# Keg_Cop_-_Eight_Straight.net
KiCad netlist of a schematic drawn in EAGLE
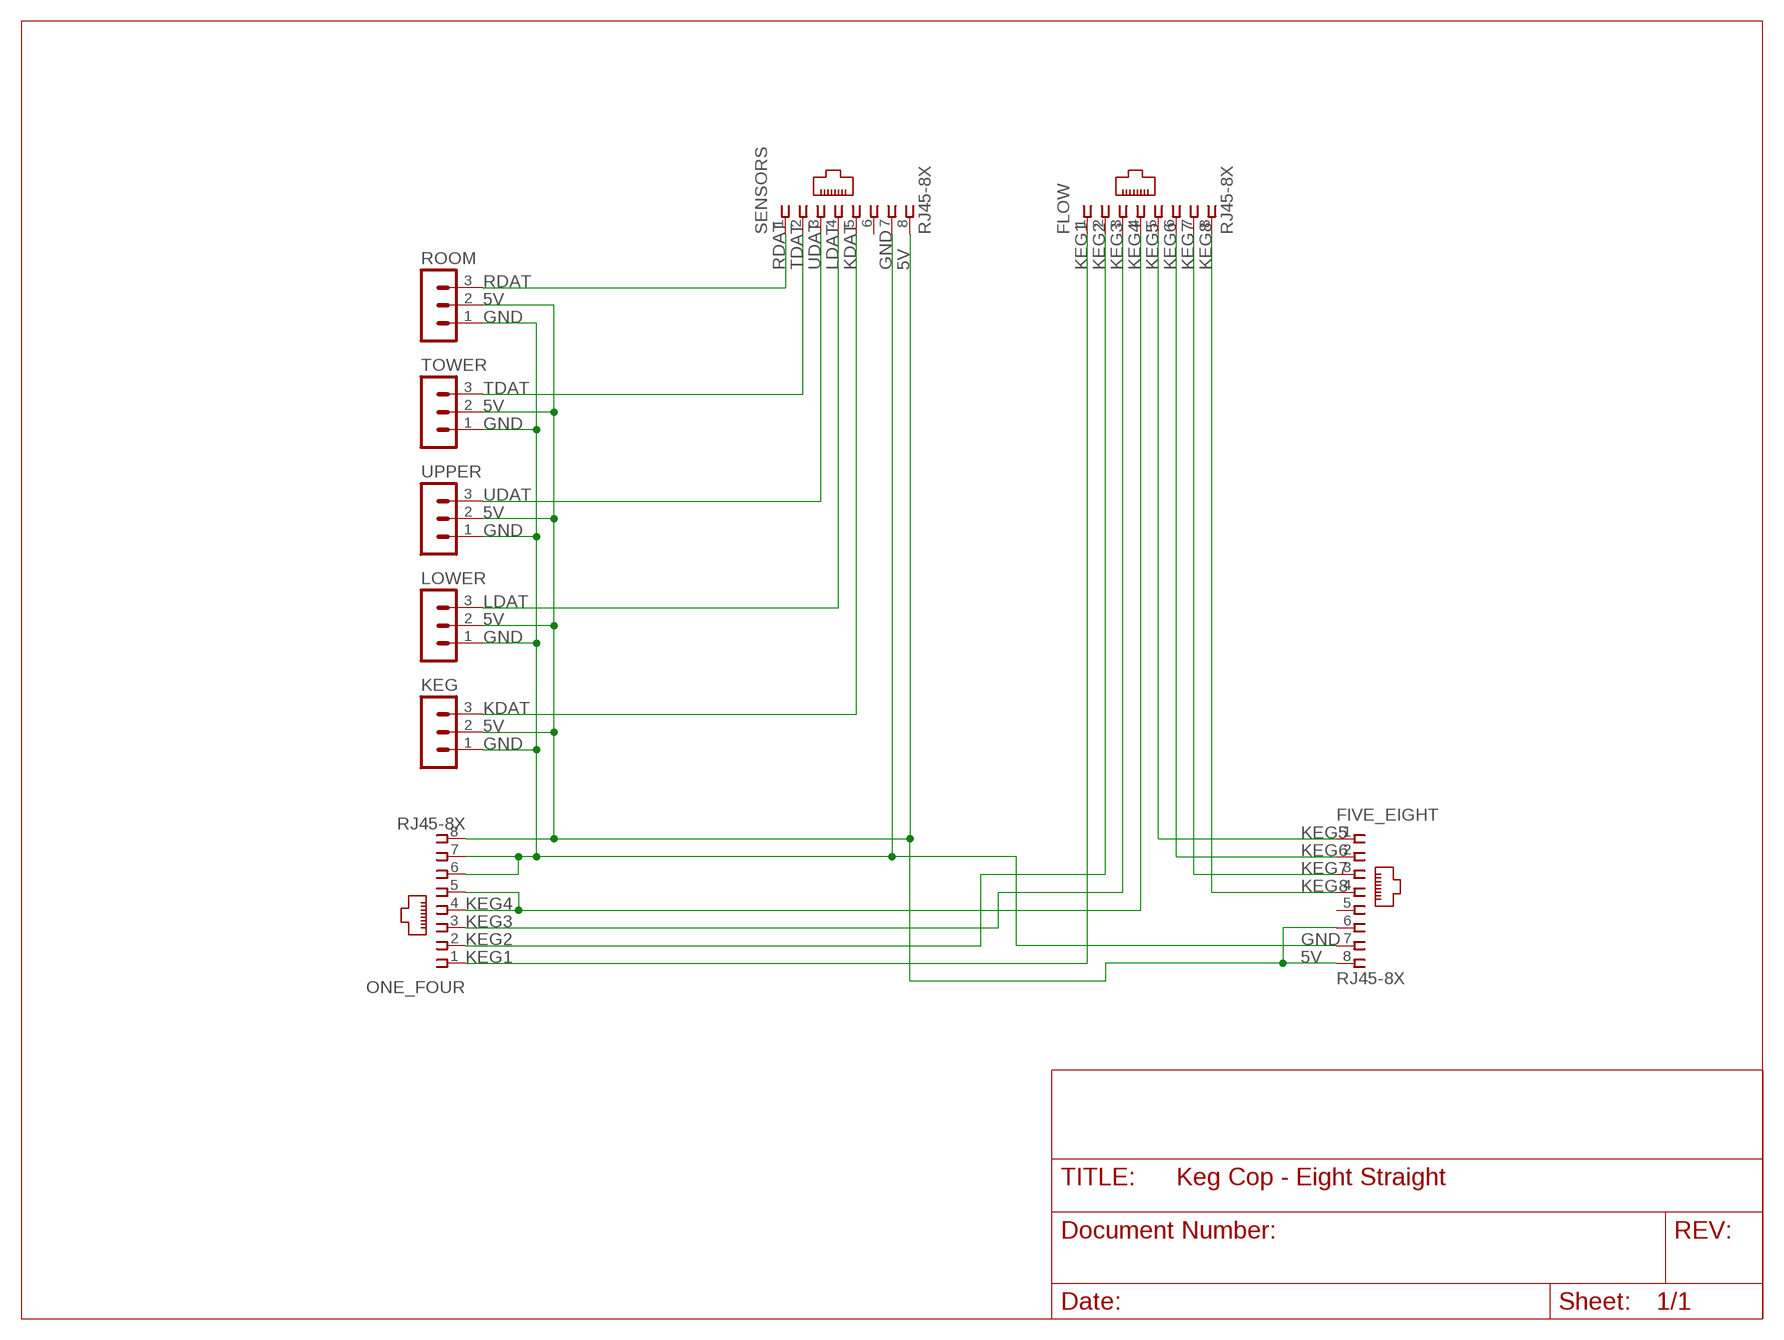
[diagram p0: schematic, sheet 1]

(export (version "E")
  (design (tool "Eeschema 10.0.6"))
  (components
    (comp (ref "FIVE_EIGHT")
      (value "RJ45-8X")
      (footprint "eagle-import:RJ45-NO-SHIELD")
      (libsource (lib "eagle-import") (part "RJ45-8X"))
    )
    (comp (ref "FLOW")
      (value "RJ45-8X")
      (footprint "eagle-import:RJ45-NO-SHIELD")
      (libsource (lib "eagle-import") (part "RJ45-8X"))
    )
    (comp (ref "KEG")
      (value "HDR-3")
      (footprint "eagle-import:HDR-3_VERT")
      (libsource (lib "eagle-import") (part "HDR-3"))
    )
    (comp (ref "LOWER")
      (value "HDR-3")
      (footprint "eagle-import:HDR-3_VERT")
      (libsource (lib "eagle-import") (part "HDR-3"))
    )
    (comp (ref "ONE_FOUR")
      (value "RJ45-8X")
      (footprint "eagle-import:RJ45-NO-SHIELD")
      (libsource (lib "eagle-import") (part "RJ45-8X"))
    )
    (comp (ref "ROOM")
      (value "HDR-3")
      (footprint "eagle-import:HDR-3_VERT")
      (libsource (lib "eagle-import") (part "HDR-3"))
    )
    (comp (ref "SENSORS")
      (value "RJ45-8X")
      (footprint "eagle-import:RJ45-NO-SHIELD")
      (libsource (lib "eagle-import") (part "RJ45-8X"))
    )
    (comp (ref "TOWER")
      (value "HDR-3")
      (footprint "eagle-import:HDR-3_VERT")
      (libsource (lib "eagle-import") (part "HDR-3"))
    )
    (comp (ref "UPPER")
      (value "HDR-3")
      (footprint "eagle-import:HDR-3_VERT")
      (libsource (lib "eagle-import") (part "HDR-3"))
    )
  )
  (nets
    (net (code "1") (name "/5V") (class "Default")
      (node (ref "FIVE_EIGHT") (pin "6") (pinfunction "6_6") (pintype "passive"))
      (node (ref "FIVE_EIGHT") (pin "8") (pinfunction "8_8") (pintype "passive"))
      (node (ref "KEG") (pin "2") (pinfunction "2_2") (pintype "passive"))
      (node (ref "LOWER") (pin "2") (pinfunction "2_2") (pintype "passive"))
      (node (ref "ONE_FOUR") (pin "8") (pinfunction "8_8") (pintype "passive"))
      (node (ref "ROOM") (pin "2") (pinfunction "2_2") (pintype "passive"))
      (node (ref "SENSORS") (pin "8") (pinfunction "8_8") (pintype "passive"))
      (node (ref "TOWER") (pin "2") (pinfunction "2_2") (pintype "passive"))
      (node (ref "UPPER") (pin "2") (pinfunction "2_2") (pintype "passive"))
    )
    (net (code "2") (name "/GND") (class "Default")
      (node (ref "FIVE_EIGHT") (pin "7") (pinfunction "7_7") (pintype "passive"))
      (node (ref "KEG") (pin "1") (pinfunction "1_1") (pintype "passive"))
      (node (ref "LOWER") (pin "1") (pinfunction "1_1") (pintype "passive"))
      (node (ref "ONE_FOUR") (pin "6") (pinfunction "6_6") (pintype "passive"))
      (node (ref "ONE_FOUR") (pin "7") (pinfunction "7_7") (pintype "passive"))
      (node (ref "ROOM") (pin "1") (pinfunction "1_1") (pintype "passive"))
      (node (ref "SENSORS") (pin "7") (pinfunction "7_7") (pintype "passive"))
      (node (ref "TOWER") (pin "1") (pinfunction "1_1") (pintype "passive"))
      (node (ref "UPPER") (pin "1") (pinfunction "1_1") (pintype "passive"))
    )
    (net (code "3") (name "/KDAT") (class "Default")
      (node (ref "KEG") (pin "3") (pinfunction "3_3") (pintype "passive"))
      (node (ref "SENSORS") (pin "5") (pinfunction "5_5") (pintype "passive"))
    )
    (net (code "4") (name "/KEG1") (class "Default")
      (node (ref "FLOW") (pin "1") (pinfunction "1_1") (pintype "passive"))
      (node (ref "ONE_FOUR") (pin "1") (pinfunction "1_1") (pintype "passive"))
    )
    (net (code "5") (name "/KEG2") (class "Default")
      (node (ref "FLOW") (pin "2") (pinfunction "2_2") (pintype "passive"))
      (node (ref "ONE_FOUR") (pin "2") (pinfunction "2_2") (pintype "passive"))
    )
    (net (code "6") (name "/KEG3") (class "Default")
      (node (ref "FLOW") (pin "3") (pinfunction "3_3") (pintype "passive"))
      (node (ref "ONE_FOUR") (pin "3") (pinfunction "3_3") (pintype "passive"))
    )
    (net (code "7") (name "/KEG4") (class "Default")
      (node (ref "FLOW") (pin "4") (pinfunction "4_4") (pintype "passive"))
      (node (ref "ONE_FOUR") (pin "4") (pinfunction "4_4") (pintype "passive"))
      (node (ref "ONE_FOUR") (pin "5") (pinfunction "5_5") (pintype "passive"))
    )
    (net (code "8") (name "/KEG5") (class "Default")
      (node (ref "FIVE_EIGHT") (pin "1") (pinfunction "1_1") (pintype "passive"))
      (node (ref "FLOW") (pin "5") (pinfunction "5_5") (pintype "passive"))
    )
    (net (code "9") (name "/KEG6") (class "Default")
      (node (ref "FIVE_EIGHT") (pin "2") (pinfunction "2_2") (pintype "passive"))
      (node (ref "FLOW") (pin "6") (pinfunction "6_6") (pintype "passive"))
    )
    (net (code "10") (name "/KEG7") (class "Default")
      (node (ref "FIVE_EIGHT") (pin "3") (pinfunction "3_3") (pintype "passive"))
      (node (ref "FLOW") (pin "7") (pinfunction "7_7") (pintype "passive"))
    )
    (net (code "11") (name "/KEG8") (class "Default")
      (node (ref "FIVE_EIGHT") (pin "4") (pinfunction "4_4") (pintype "passive"))
      (node (ref "FLOW") (pin "8") (pinfunction "8_8") (pintype "passive"))
    )
    (net (code "12") (name "/LDAT") (class "Default")
      (node (ref "LOWER") (pin "3") (pinfunction "3_3") (pintype "passive"))
      (node (ref "SENSORS") (pin "4") (pinfunction "4_4") (pintype "passive"))
    )
    (net (code "13") (name "/RDAT") (class "Default")
      (node (ref "ROOM") (pin "3") (pinfunction "3_3") (pintype "passive"))
      (node (ref "SENSORS") (pin "1") (pinfunction "1_1") (pintype "passive"))
    )
    (net (code "14") (name "/TDAT") (class "Default")
      (node (ref "SENSORS") (pin "2") (pinfunction "2_2") (pintype "passive"))
      (node (ref "TOWER") (pin "3") (pinfunction "3_3") (pintype "passive"))
    )
    (net (code "15") (name "/UDAT") (class "Default")
      (node (ref "SENSORS") (pin "3") (pinfunction "3_3") (pintype "passive"))
      (node (ref "UPPER") (pin "3") (pinfunction "3_3") (pintype "passive"))
    )
    (net (code "16") (name "unconnected-(FIVE_EIGHT-Pad5)") (class "Default")
      (node (ref "FIVE_EIGHT") (pin "5") (pinfunction "5_5") (pintype "passive"))
    )
    (net (code "17") (name "unconnected-(SENSORS-Pad6)") (class "Default")
      (node (ref "SENSORS") (pin "6") (pinfunction "6_6") (pintype "passive"))
    )
  )
)
